# OpenRing_Debug_DEBUG.net
KiCad netlist of a schematic drawn in Altium Designer
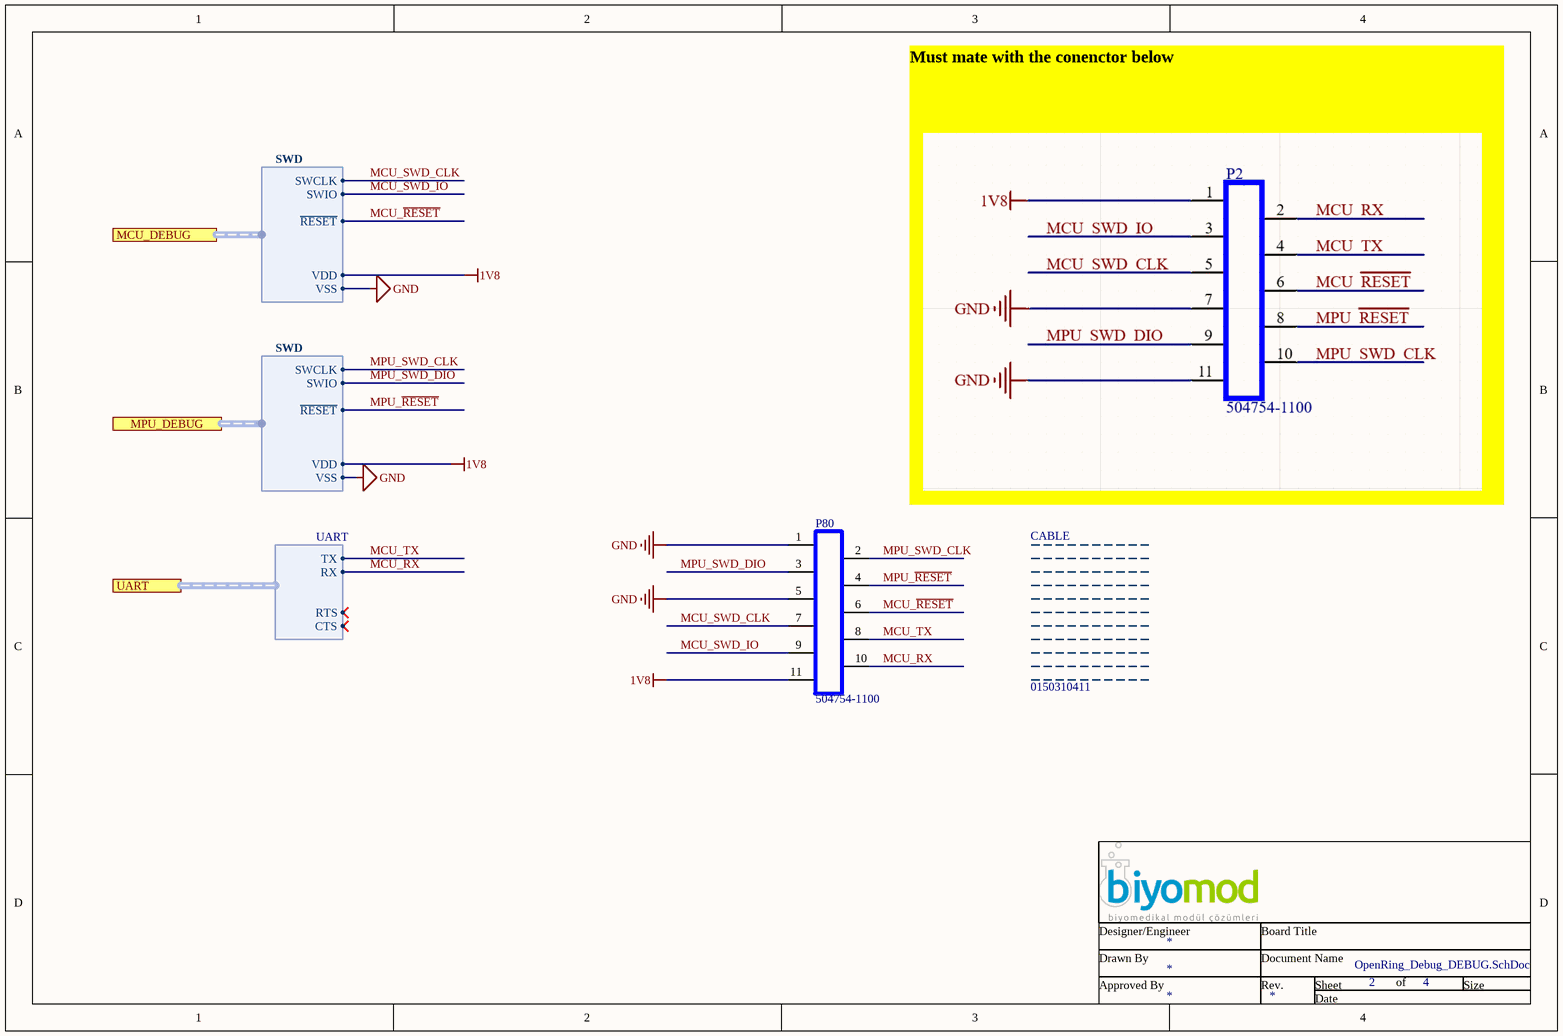
[diagram p0: OpenRing_Debug_DEBUG.SchDoc]

(export (version "E")
  (design (tool "Eeschema 10.0.6"))
  (components
    (comp (ref "CABLE")
      (value "0150310411")
      (fields (field (name "MANUFACTURER") "Molex"))
      (libsource (lib "OpenRingComponents") (part "0150310411"))
    )
    (comp (ref "P80")
      (value "504754-1100")
      (footprint "5047541100")
      (description "Conn FFC/FPC Connector SKT 11 POS 0.3mm Solder RA SMD Easy-On™ T/R")
      (fields (field (name "MANUFACTURER") "Molex") (field (name "CHECKED") "FALSE"))
      (libsource (lib "Connectors") (part "504754-1100"))
    )
  )
  (nets
    (net (code "3") (name "/MCU_RX") (class "Default")
      (node (ref "P80") (pin "10") (pinfunction "10_10") (pintype "passive"))
    )
    (net (code "4") (name "/MCU_SWD_CLK") (class "Default")
      (node (ref "P80") (pin "7") (pinfunction "7_7") (pintype "passive"))
    )
    (net (code "5") (name "/MCU_SWD_IO") (class "Default")
      (node (ref "P80") (pin "9") (pinfunction "9_9") (pintype "passive"))
    )
    (net (code "6") (name "/MCU_TX") (class "Default")
      (node (ref "P80") (pin "8") (pinfunction "8_8") (pintype "passive"))
    )
    (net (code "7") (name "/MCU_~{RESET}") (class "Default")
      (node (ref "P80") (pin "6") (pinfunction "6_6") (pintype "passive"))
    )
    (net (code "8") (name "/MPU_SWD_CLK") (class "Default")
      (node (ref "P80") (pin "2") (pinfunction "2_2") (pintype "passive"))
    )
    (net (code "9") (name "/MPU_SWD_DIO") (class "Default")
      (node (ref "P80") (pin "3") (pinfunction "3_3") (pintype "passive"))
    )
    (net (code "10") (name "/MPU_~{RESET}") (class "Default")
      (node (ref "P80") (pin "4") (pinfunction "4_4") (pintype "passive"))
    )
    (net (code "13") (name "1V8") (class "Default")
      (node (ref "P80") (pin "11") (pinfunction "11_11") (pintype "passive"))
    )
    (net (code "14") (name "GND") (class "Default")
      (node (ref "P80") (pin "1") (pinfunction "1_1") (pintype "passive"))
      (node (ref "P80") (pin "5") (pinfunction "5_5") (pintype "passive"))
    )
  )
)
